# powerSupplyV1.net
KiCad netlist of a schematic drawn in EAGLE
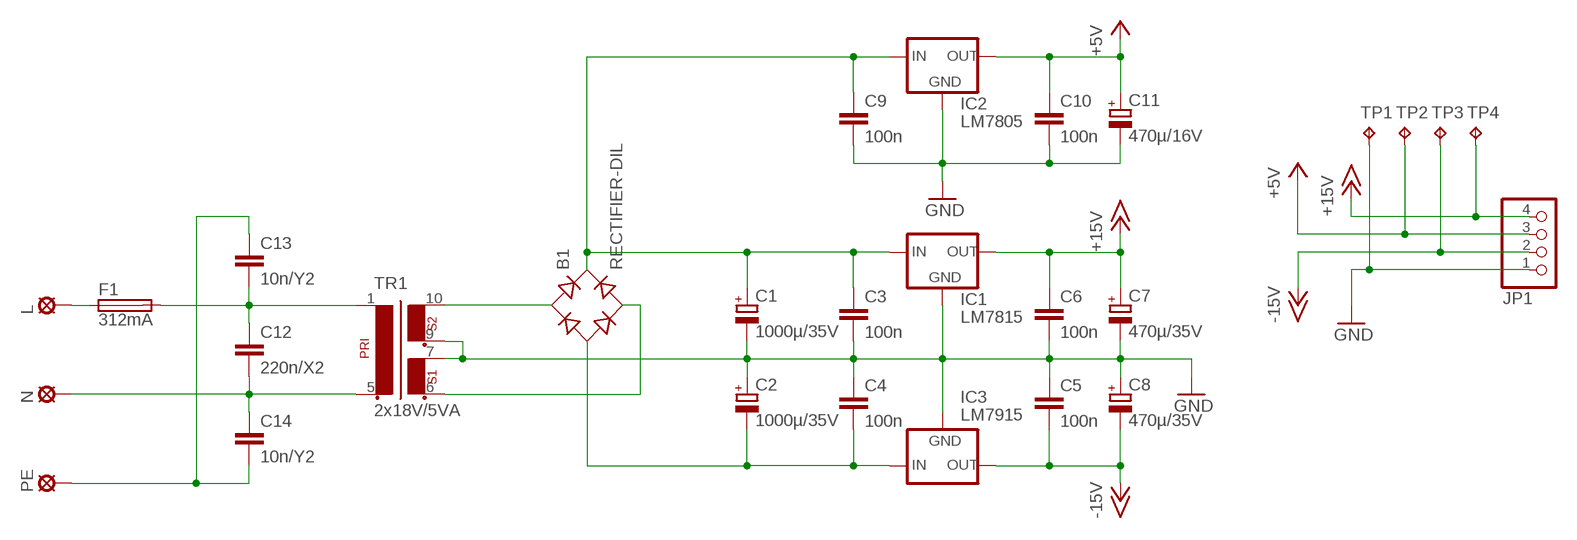
[diagram p0: schematic, sheet 1]

(export (version "E")
  (design (tool "Eeschema 10.0.6"))
  (components
    (comp (ref "B1")
      (value "RECTIFIER-DIL")
      (footprint "eagle-import:B-DIL")
      (libsource (lib "eagle-import") (part "RECTIFIER-DIL"))
    )
    (comp (ref "C1")
      (value "1000µ/35V")
      (footprint "eagle-import:E5-13")
      (libsource (lib "eagle-import") (part "CPOL-EUE5-13"))
    )
    (comp (ref "C2")
      (value "1000µ/35V")
      (footprint "eagle-import:E5-13")
      (libsource (lib "eagle-import") (part "CPOL-EUE5-13"))
    )
    (comp (ref "C3")
      (value "100n")
      (footprint "eagle-import:C0603K")
      (libsource (lib "eagle-import") (part "C-EUC0603K"))
    )
    (comp (ref "C4")
      (value "100n")
      (footprint "eagle-import:C0603K")
      (libsource (lib "eagle-import") (part "C-EUC0603K"))
    )
    (comp (ref "C5")
      (value "100n")
      (footprint "eagle-import:C0603K")
      (libsource (lib "eagle-import") (part "C-EUC0603K"))
    )
    (comp (ref "C6")
      (value "100n")
      (footprint "eagle-import:C0603K")
      (libsource (lib "eagle-import") (part "C-EUC0603K"))
    )
    (comp (ref "C7")
      (value "470µ/35V")
      (footprint "eagle-import:E5-10,5")
      (libsource (lib "eagle-import") (part "CPOL-EUE5-10.5"))
    )
    (comp (ref "C8")
      (value "470µ/35V")
      (footprint "eagle-import:E5-10,5")
      (libsource (lib "eagle-import") (part "CPOL-EUE5-10.5"))
    )
    (comp (ref "C9")
      (value "100n")
      (footprint "eagle-import:C0603K")
      (libsource (lib "eagle-import") (part "C-EUC0603K"))
    )
    (comp (ref "C10")
      (value "100n")
      (footprint "eagle-import:C0603K")
      (libsource (lib "eagle-import") (part "C-EUC0603K"))
    )
    (comp (ref "C11")
      (value "470µ/16V")
      (footprint "eagle-import:E5-10,5")
      (libsource (lib "eagle-import") (part "CPOL-EUE5-10.5"))
    )
    (comp (ref "C12")
      (value "220n/X2")
      (footprint "eagle-import:C225-062X268")
      (libsource (lib "eagle-import") (part "C-EU225-062X268"))
    )
    (comp (ref "C13")
      (value "10n/Y2")
      (footprint "eagle-import:C150-054X183")
      (libsource (lib "eagle-import") (part "C-EU150-054X183"))
    )
    (comp (ref "C14")
      (value "10n/Y2")
      (footprint "eagle-import:C150-054X183")
      (libsource (lib "eagle-import") (part "C-EU150-054X183"))
    )
    (comp (ref "F1")
      (value "312mA")
      (footprint "eagle-import:SH22,5")
      (fields (field (name "MF") "SCHURTER") (field (name "MPN") "0031.8201"))
      (libsource (lib "eagle-import") (part "SH22,5"))
    )
    (comp (ref "IC1")
      (value "LM7815")
      (footprint "eagle-import:78XXS")
      (libsource (lib "eagle-import") (part "78XXS"))
    )
    (comp (ref "IC2")
      (value "LM7805")
      (footprint "eagle-import:78XXS")
      (libsource (lib "eagle-import") (part "78XXS"))
    )
    (comp (ref "IC3")
      (value "LM7915")
      (footprint "eagle-import:79XXS")
      (libsource (lib "eagle-import") (part "79XXS"))
    )
    (comp (ref "JP1")
      (value "PINHD-1X4")
      (footprint "eagle-import:1X04")
      (libsource (lib "eagle-import") (part "PINHD-1X4"))
    )
    (comp (ref "L")
      (value "L")
      (footprint "eagle-import:SE14")
      (libsource (lib "eagle-import") (part "SE14"))
    )
    (comp (ref "N")
      (value "SE14")
      (footprint "eagle-import:SE14")
      (libsource (lib "eagle-import") (part "SE14"))
    )
    (comp (ref "PE")
      (value "SE14")
      (footprint "eagle-import:SE14")
      (libsource (lib "eagle-import") (part "SE14"))
    )
    (comp (ref "TP1")
      (value "TPB2,54")
      (footprint "eagle-import:B2,54")
      (libsource (lib "eagle-import") (part "TPB2,54"))
    )
    (comp (ref "TP2")
      (value "TPB2,54")
      (footprint "eagle-import:B2,54")
      (libsource (lib "eagle-import") (part "TPB2,54"))
    )
    (comp (ref "TP3")
      (value "TPB2,54")
      (footprint "eagle-import:B2,54")
      (libsource (lib "eagle-import") (part "TPB2,54"))
    )
    (comp (ref "TP4")
      (value "TPB2,54")
      (footprint "eagle-import:B2,54")
      (libsource (lib "eagle-import") (part "TPB2,54"))
    )
    (comp (ref "TR1")
      (value "2x18V/5VA")
      (footprint "eagle-import:EI42-2")
      (libsource (lib "eagle-import") (part "EI42-2"))
    )
  )
  (nets
    (net (code "1") (name "+5V") (class "Default")
      (node (ref "C10") (pin "1") (pinfunction "1_1") (pintype "passive"))
      (node (ref "C11") (pin "+") (pinfunction "+_+") (pintype "passive"))
      (node (ref "IC2") (pin "OUT") (pinfunction "OUT_OUT") (pintype "passive"))
      (node (ref "JP1") (pin "3") (pinfunction "3_3") (pintype "passive"))
      (node (ref "TP2") (pin "TP") (pinfunction "TP_TP") (pintype "input"))
    )
    (net (code "2") (name "+15V") (class "Default")
      (node (ref "C6") (pin "1") (pinfunction "1_1") (pintype "passive"))
      (node (ref "C7") (pin "+") (pinfunction "+_+") (pintype "passive"))
      (node (ref "IC1") (pin "OUT") (pinfunction "OUT_OUT") (pintype "passive"))
      (node (ref "JP1") (pin "4") (pinfunction "4_4") (pintype "passive"))
      (node (ref "TP4") (pin "TP") (pinfunction "TP_TP") (pintype "input"))
    )
    (net (code "3") (name "-15V") (class "Default")
      (node (ref "C5") (pin "2") (pinfunction "2_2") (pintype "passive"))
      (node (ref "C8") (pin "-") (pinfunction "-_-") (pintype "passive"))
      (node (ref "IC3") (pin "OUT") (pinfunction "OUT_OUT") (pintype "passive"))
      (node (ref "JP1") (pin "2") (pinfunction "2_2") (pintype "passive"))
      (node (ref "TP3") (pin "TP") (pinfunction "TP_TP") (pintype "input"))
    )
    (net (code "4") (name "GND") (class "Default")
      (node (ref "C1") (pin "-") (pinfunction "-_-") (pintype "passive"))
      (node (ref "C10") (pin "2") (pinfunction "2_2") (pintype "passive"))
      (node (ref "C11") (pin "-") (pinfunction "-_-") (pintype "passive"))
      (node (ref "C2") (pin "+") (pinfunction "+_+") (pintype "passive"))
      (node (ref "C3") (pin "2") (pinfunction "2_2") (pintype "passive"))
      (node (ref "C4") (pin "1") (pinfunction "1_1") (pintype "passive"))
      (node (ref "C5") (pin "1") (pinfunction "1_1") (pintype "passive"))
      (node (ref "C6") (pin "2") (pinfunction "2_2") (pintype "passive"))
      (node (ref "C7") (pin "-") (pinfunction "-_-") (pintype "passive"))
      (node (ref "C8") (pin "+") (pinfunction "+_+") (pintype "passive"))
      (node (ref "C9") (pin "2") (pinfunction "2_2") (pintype "passive"))
      (node (ref "IC1") (pin "GND") (pinfunction "GND_GND") (pintype "input"))
      (node (ref "IC2") (pin "GND") (pinfunction "GND_GND") (pintype "input"))
      (node (ref "IC3") (pin "GND") (pinfunction "GND_GND") (pintype "input"))
      (node (ref "JP1") (pin "1") (pinfunction "1_1") (pintype "passive"))
      (node (ref "TP1") (pin "TP") (pinfunction "TP_TP") (pintype "input"))
      (node (ref "TR1") (pin "7") (pinfunction "4_7") (pintype "passive"))
      (node (ref "TR1") (pin "9") (pinfunction "5_9") (pintype "passive"))
    )
    (net (code "5") (name "Net-(B1-Pad+)") (class "Default")
      (node (ref "B1") (pin "+") (pinfunction "+_+") (pintype "passive"))
      (node (ref "C1") (pin "+") (pinfunction "+_+") (pintype "passive"))
      (node (ref "C3") (pin "1") (pinfunction "1_1") (pintype "passive"))
      (node (ref "C9") (pin "1") (pinfunction "1_1") (pintype "passive"))
      (node (ref "IC1") (pin "IN") (pinfunction "IN_IN") (pintype "input"))
      (node (ref "IC2") (pin "IN") (pinfunction "IN_IN") (pintype "input"))
    )
    (net (code "6") (name "Net-(B1-Pad-)") (class "Default")
      (node (ref "B1") (pin "-") (pinfunction "-_-") (pintype "passive"))
      (node (ref "C2") (pin "-") (pinfunction "-_-") (pintype "passive"))
      (node (ref "C4") (pin "2") (pinfunction "2_2") (pintype "passive"))
      (node (ref "IC3") (pin "IN") (pinfunction "IN_IN") (pintype "input"))
    )
    (net (code "7") (name "Net-(C12-Pad1)") (class "Default")
      (node (ref "C12") (pin "1") (pinfunction "1_1") (pintype "passive"))
      (node (ref "C13") (pin "2") (pinfunction "2_2") (pintype "passive"))
      (node (ref "F1") (pin "2") (pinfunction "2_2") (pintype "passive"))
      (node (ref "TR1") (pin "1") (pinfunction "1_1") (pintype "passive"))
    )
    (net (code "8") (name "Net-(C13-Pad1)") (class "Default")
      (node (ref "C13") (pin "1") (pinfunction "1_1") (pintype "passive"))
      (node (ref "C14") (pin "2") (pinfunction "2_2") (pintype "passive"))
      (node (ref "PE") (pin "MP") (pinfunction "MP_MP") (pintype "passive"))
    )
    (net (code "9") (name "Net-(F1-Pad1)") (class "Default")
      (node (ref "F1") (pin "1") (pinfunction "1_1") (pintype "passive"))
      (node (ref "L") (pin "MP") (pinfunction "MP_MP") (pintype "passive"))
    )
    (net (code "10") (name "Net-(TR1-2)") (class "Default")
      (node (ref "C12") (pin "2") (pinfunction "2_2") (pintype "passive"))
      (node (ref "C14") (pin "1") (pinfunction "1_1") (pintype "passive"))
      (node (ref "N") (pin "MP") (pinfunction "MP_MP") (pintype "passive"))
      (node (ref "TR1") (pin "5") (pinfunction "2_5") (pintype "passive"))
    )
    (net (code "11") (name "Net-(TR1-3)") (class "Default")
      (node (ref "B1") (pin "AC2") (pinfunction "AC2_AC2") (pintype "passive"))
      (node (ref "TR1") (pin "6") (pinfunction "3_6") (pintype "passive"))
    )
    (net (code "12") (name "Net-(TR1-6)") (class "Default")
      (node (ref "B1") (pin "AC1") (pinfunction "AC1_AC1") (pintype "passive"))
      (node (ref "TR1") (pin "10") (pinfunction "6_10") (pintype "passive"))
    )
  )
)
